# HMC624A.net
KiCad netlist of a schematic drawn in Altium Designer
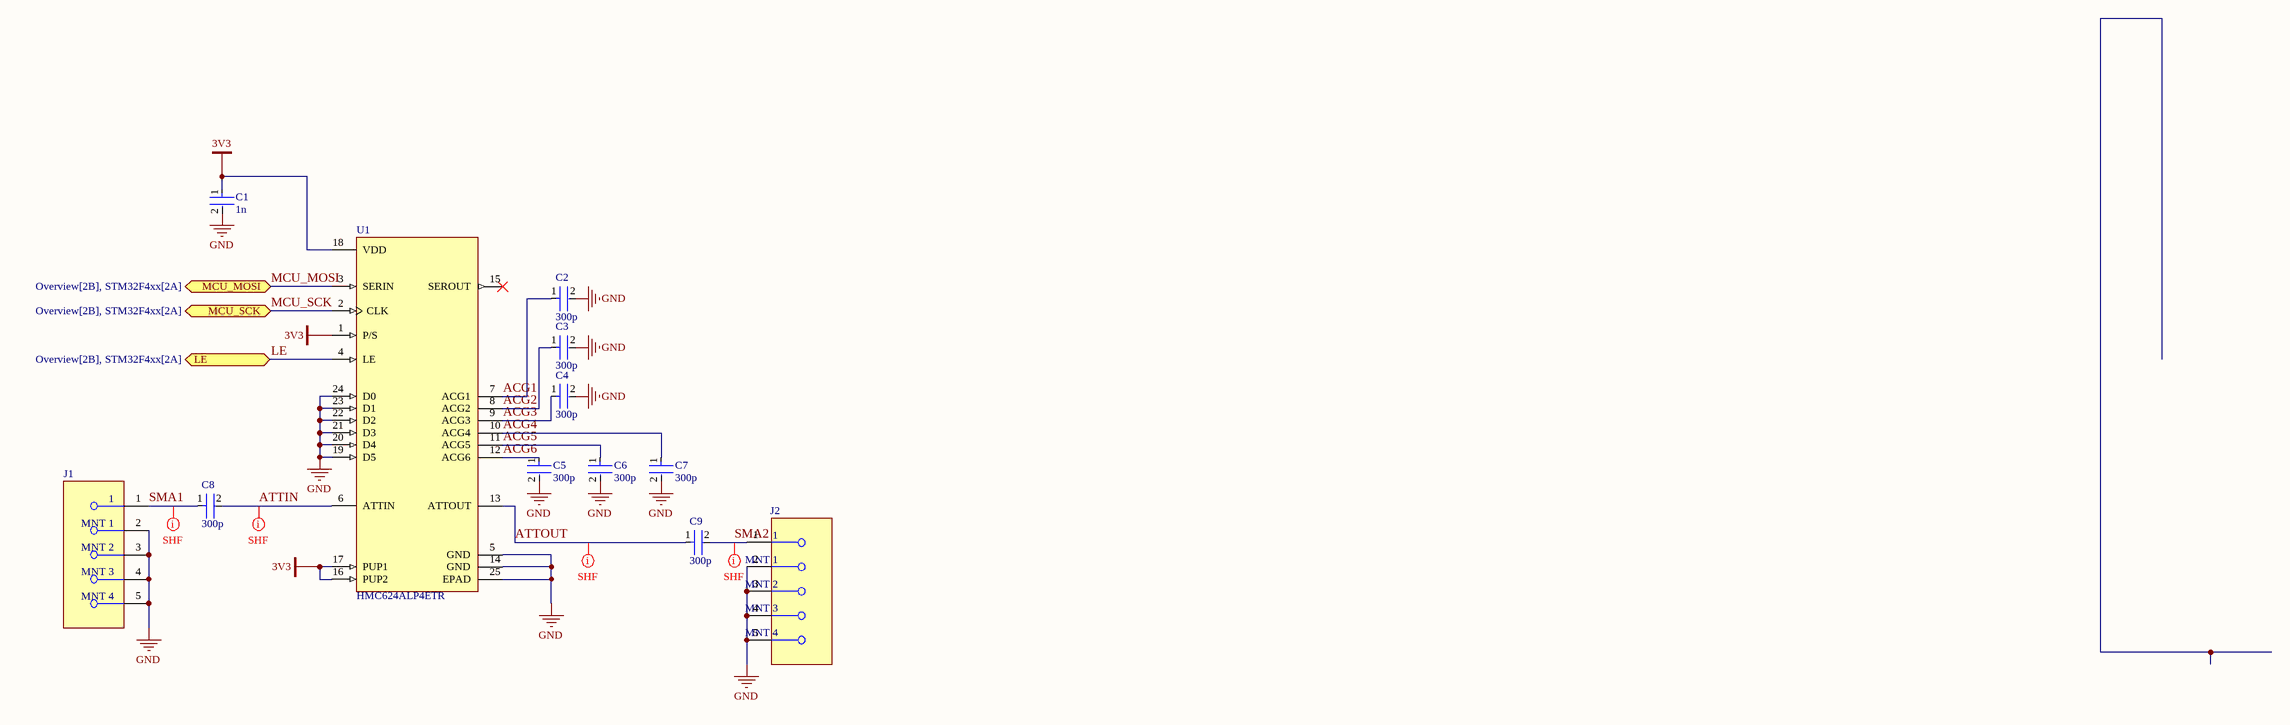
[diagram p0: HMC624A.SchDoc]

(export (version "E")
  (design (tool "Eeschema 10.0.6"))
  (components
    (comp (ref "C1")
      (value "1n")
      (footprint "FP-C0402-BB-MFG")
      (description "Cap Ceramic 0.001uF 50V X7R 10% Pad SMD 0402 125C Automotive T/R")
      (fields
        (field (name "MANUFACTURER") "Kemet")
        (field (name "OCTOPART") "https://octopart.com/c0402c102k5racauto-kemet-34852013")
      )
      (libsource (lib "Altium Content Vault") (part "b4654b650e69147ec39a6b967a45e02"))
    )
    (comp (ref "C2")
      (value "300p")
      (footprint "FP-CC0402-MFG")
      (description "CC0402 330 pF X7R 10.00% 25 V")
      (fields
        (field (name "MANUFACTURER PART NUMBER") "CC0402KRX7R8BB331")
        (field (name "MANUFACTURER") "YAGEO")
      )
      (libsource (lib "Altium Content Vault") (part "11868f565c42a9108669ba33697ecf6"))
    )
    (comp (ref "C3")
      (value "300p")
      (footprint "FP-CC0402-MFG")
      (description "CC0402 330 pF X7R 10.00% 25 V")
      (fields
        (field (name "MANUFACTURER PART NUMBER") "CC0402KRX7R8BB331")
        (field (name "MANUFACTURER") "YAGEO")
      )
      (libsource (lib "Altium Content Vault") (part "11868f565c42a9108669ba33697ecf6"))
    )
    (comp (ref "C4")
      (value "300p")
      (footprint "FP-CC0402-MFG")
      (description "CC0402 330 pF X7R 10.00% 25 V")
      (fields
        (field (name "MANUFACTURER PART NUMBER") "CC0402KRX7R8BB331")
        (field (name "MANUFACTURER") "YAGEO")
      )
      (libsource (lib "Altium Content Vault") (part "11868f565c42a9108669ba33697ecf6"))
    )
    (comp (ref "C5")
      (value "300p")
      (footprint "FP-CC0402-MFG")
      (description "CC0402 330 pF X7R 10.00% 25 V")
      (fields
        (field (name "MANUFACTURER PART NUMBER") "CC0402KRX7R8BB331")
        (field (name "MANUFACTURER") "YAGEO")
      )
      (libsource (lib "Altium Content Vault") (part "11868f565c42a9108669ba33697ecf6"))
    )
    (comp (ref "C6")
      (value "300p")
      (footprint "FP-CC0402-MFG")
      (description "CC0402 330 pF X7R 10.00% 25 V")
      (fields
        (field (name "MANUFACTURER PART NUMBER") "CC0402KRX7R8BB331")
        (field (name "MANUFACTURER") "YAGEO")
      )
      (libsource (lib "Altium Content Vault") (part "11868f565c42a9108669ba33697ecf6"))
    )
    (comp (ref "C7")
      (value "300p")
      (footprint "FP-CC0402-MFG")
      (description "CC0402 330 pF X7R 10.00% 25 V")
      (fields
        (field (name "MANUFACTURER PART NUMBER") "CC0402KRX7R8BB331")
        (field (name "MANUFACTURER") "YAGEO")
      )
      (libsource (lib "Altium Content Vault") (part "11868f565c42a9108669ba33697ecf6"))
    )
    (comp (ref "C8")
      (value "300p")
      (footprint "FP-CC0402-MFG")
      (description "CC0402 330 pF X7R 10.00% 25 V")
      (fields
        (field (name "MANUFACTURER PART NUMBER") "CC0402KRX7R8BB331")
        (field (name "MANUFACTURER") "YAGEO")
      )
      (libsource (lib "Altium Content Vault") (part "11868f565c42a9108669ba33697ecf6"))
    )
    (comp (ref "C9")
      (value "300p")
      (footprint "FP-CC0402-MFG")
      (description "CC0402 330 pF X7R 10.00% 25 V")
      (fields
        (field (name "MANUFACTURER PART NUMBER") "CC0402KRX7R8BB331")
        (field (name "MANUFACTURER") "YAGEO")
      )
      (libsource (lib "Altium Content Vault") (part "11868f565c42a9108669ba33697ecf6"))
    )
    (comp (ref "J1")
      (value "CON-SMA-EDGE-S")
      (footprint "FP-CON-SMA-EDGE-S-MFG")
      (description "CONN SMA JACK STR EDGE MNT")
      (fields
        (field (name "OCTOPART") "https://octopart.com/con-sma-edge-s-rf+solutions-70967450")
        (field (name "MANUFACTURER") "RF Solutions Ltd.")
      )
      (libsource (lib "") (part "a163d97a771fcdd2fd1f1a9264c171f_1"))
    )
    (comp (ref "J2")
      (value "CON-SMA-EDGE-S")
      (footprint "FP-CON-SMA-EDGE-S-MFG")
      (description "CONN SMA JACK STR EDGE MNT")
      (fields
        (field (name "OCTOPART") "https://octopart.com/con-sma-edge-s-rf+solutions-70967450")
        (field (name "MANUFACTURER") "RF Solutions Ltd.")
      )
      (libsource (lib "Altium Content Vault") (part "a163d97a771fcdd2fd1f1a9264c171f"))
    )
    (comp (ref "U1")
      (value "HMC624ALP4ETR")
      (footprint "FP-CP-24-16-IPC_C")
      (description "RF ATTENUATOR 31.5DB 50OHM 24QFN")
      (fields
        (field (name "MANUFACTURER") "Analog Devices")
        (field (name "OCTOPART") "https://octopart.com/hmc624alp4etr-analog+devices-51967055")
      )
      (libsource (lib "Altium Content Vault") (part "1be31628466b451d82ecfcea0e56310"))
    )
  )
  (nets
    (net (code "1") (name "/ACG1") (class "Default")
      (node (ref "C2") (pin "1") (pinfunction "1_1") (pintype "passive"))
      (node (ref "U1") (pin "7") (pinfunction "ACG1_7") (pintype "passive"))
    )
    (net (code "2") (name "/ACG2") (class "Default")
      (node (ref "C3") (pin "1") (pinfunction "1_1") (pintype "passive"))
      (node (ref "U1") (pin "8") (pinfunction "ACG2_8") (pintype "passive"))
    )
    (net (code "3") (name "/ACG3") (class "Default")
      (node (ref "C4") (pin "1") (pinfunction "1_1") (pintype "passive"))
      (node (ref "U1") (pin "9") (pinfunction "ACG3_9") (pintype "passive"))
    )
    (net (code "4") (name "/ACG4") (class "Default")
      (node (ref "C7") (pin "1") (pinfunction "1_1") (pintype "passive"))
      (node (ref "U1") (pin "10") (pinfunction "ACG4_10") (pintype "passive"))
    )
    (net (code "5") (name "/ACG5") (class "Default")
      (node (ref "C6") (pin "1") (pinfunction "1_1") (pintype "passive"))
      (node (ref "U1") (pin "11") (pinfunction "ACG5_11") (pintype "passive"))
    )
    (net (code "6") (name "/ACG6") (class "Default")
      (node (ref "C5") (pin "1") (pinfunction "1_1") (pintype "passive"))
      (node (ref "U1") (pin "12") (pinfunction "ACG6_12") (pintype "passive"))
    )
    (net (code "7") (name "/ATTIN") (class "Default")
      (node (ref "C8") (pin "2") (pinfunction "2_2") (pintype "passive"))
      (node (ref "U1") (pin "6") (pinfunction "ATTIN_6") (pintype "passive"))
    )
    (net (code "8") (name "/ATTOUT") (class "Default")
      (node (ref "C9") (pin "1") (pinfunction "1_1") (pintype "passive"))
      (node (ref "U1") (pin "13") (pinfunction "ATTOUT_13") (pintype "passive"))
    )
    (net (code "9") (name "/LE") (class "Default")
      (node (ref "U1") (pin "4") (pinfunction "LE_4") (pintype "input"))
    )
    (net (code "10") (name "/MCU_MOSI") (class "Default")
      (node (ref "U1") (pin "3") (pinfunction "SERIN_3") (pintype "input"))
    )
    (net (code "11") (name "/MCU_SCK") (class "Default")
      (node (ref "U1") (pin "2") (pinfunction "CLK_2") (pintype "input"))
    )
    (net (code "12") (name "/SMA1") (class "Default")
      (node (ref "C8") (pin "1") (pinfunction "1_1") (pintype "passive"))
      (node (ref "J1") (pin "1") (pinfunction "1_1") (pintype "passive"))
    )
    (net (code "13") (name "/SMA2") (class "Default")
      (node (ref "C9") (pin "2") (pinfunction "2_2") (pintype "passive"))
      (node (ref "J2") (pin "1") (pinfunction "1_1") (pintype "passive"))
    )
    (net (code "14") (name "3V3") (class "Default")
      (node (ref "C1") (pin "1") (pinfunction "1_1") (pintype "passive"))
      (node (ref "U1") (pin "1") (pinfunction "P/S_1") (pintype "input"))
      (node (ref "U1") (pin "16") (pinfunction "PUP2_16") (pintype "input"))
      (node (ref "U1") (pin "17") (pinfunction "PUP1_17") (pintype "input"))
      (node (ref "U1") (pin "18") (pinfunction "VDD_18") (pintype "power_in"))
    )
    (net (code "15") (name "GND") (class "Default")
      (node (ref "C1") (pin "2") (pinfunction "2_2") (pintype "passive"))
      (node (ref "C2") (pin "2") (pinfunction "2_2") (pintype "passive"))
      (node (ref "C3") (pin "2") (pinfunction "2_2") (pintype "passive"))
      (node (ref "C4") (pin "2") (pinfunction "2_2") (pintype "passive"))
      (node (ref "C5") (pin "2") (pinfunction "2_2") (pintype "passive"))
      (node (ref "C6") (pin "2") (pinfunction "2_2") (pintype "passive"))
      (node (ref "C7") (pin "2") (pinfunction "2_2") (pintype "passive"))
      (node (ref "J1") (pin "2") (pinfunction "MNT_1_2") (pintype "passive"))
      (node (ref "J1") (pin "3") (pinfunction "MNT_2_3") (pintype "passive"))
      (node (ref "J1") (pin "4") (pinfunction "MNT_3_4") (pintype "passive"))
      (node (ref "J1") (pin "5") (pinfunction "MNT_4_5") (pintype "passive"))
      (node (ref "J2") (pin "2") (pinfunction "MNT_1_2") (pintype "passive"))
      (node (ref "J2") (pin "3") (pinfunction "MNT_2_3") (pintype "passive"))
      (node (ref "J2") (pin "4") (pinfunction "MNT_3_4") (pintype "passive"))
      (node (ref "J2") (pin "5") (pinfunction "MNT_4_5") (pintype "passive"))
      (node (ref "U1") (pin "14") (pinfunction "GND_14") (pintype "power_in"))
      (node (ref "U1") (pin "19") (pinfunction "D5_19") (pintype "input"))
      (node (ref "U1") (pin "20") (pinfunction "D4_20") (pintype "input"))
      (node (ref "U1") (pin "21") (pinfunction "D3_21") (pintype "input"))
      (node (ref "U1") (pin "22") (pinfunction "D2_22") (pintype "input"))
      (node (ref "U1") (pin "23") (pinfunction "D1_23") (pintype "input"))
      (node (ref "U1") (pin "24") (pinfunction "D0_24") (pintype "input"))
      (node (ref "U1") (pin "25") (pinfunction "EPAD_25") (pintype "power_in"))
      (node (ref "U1") (pin "5") (pinfunction "GND_5") (pintype "power_in"))
    )
    (net (code "16") (name "unconnected-(U1-SEROUT-Pad15)") (class "Default")
      (node (ref "U1") (pin "15") (pinfunction "SEROUT_15") (pintype "output+no_connect"))
    )
  )
)
